# motor.net
KiCad netlist of a schematic drawn in Altium Designer
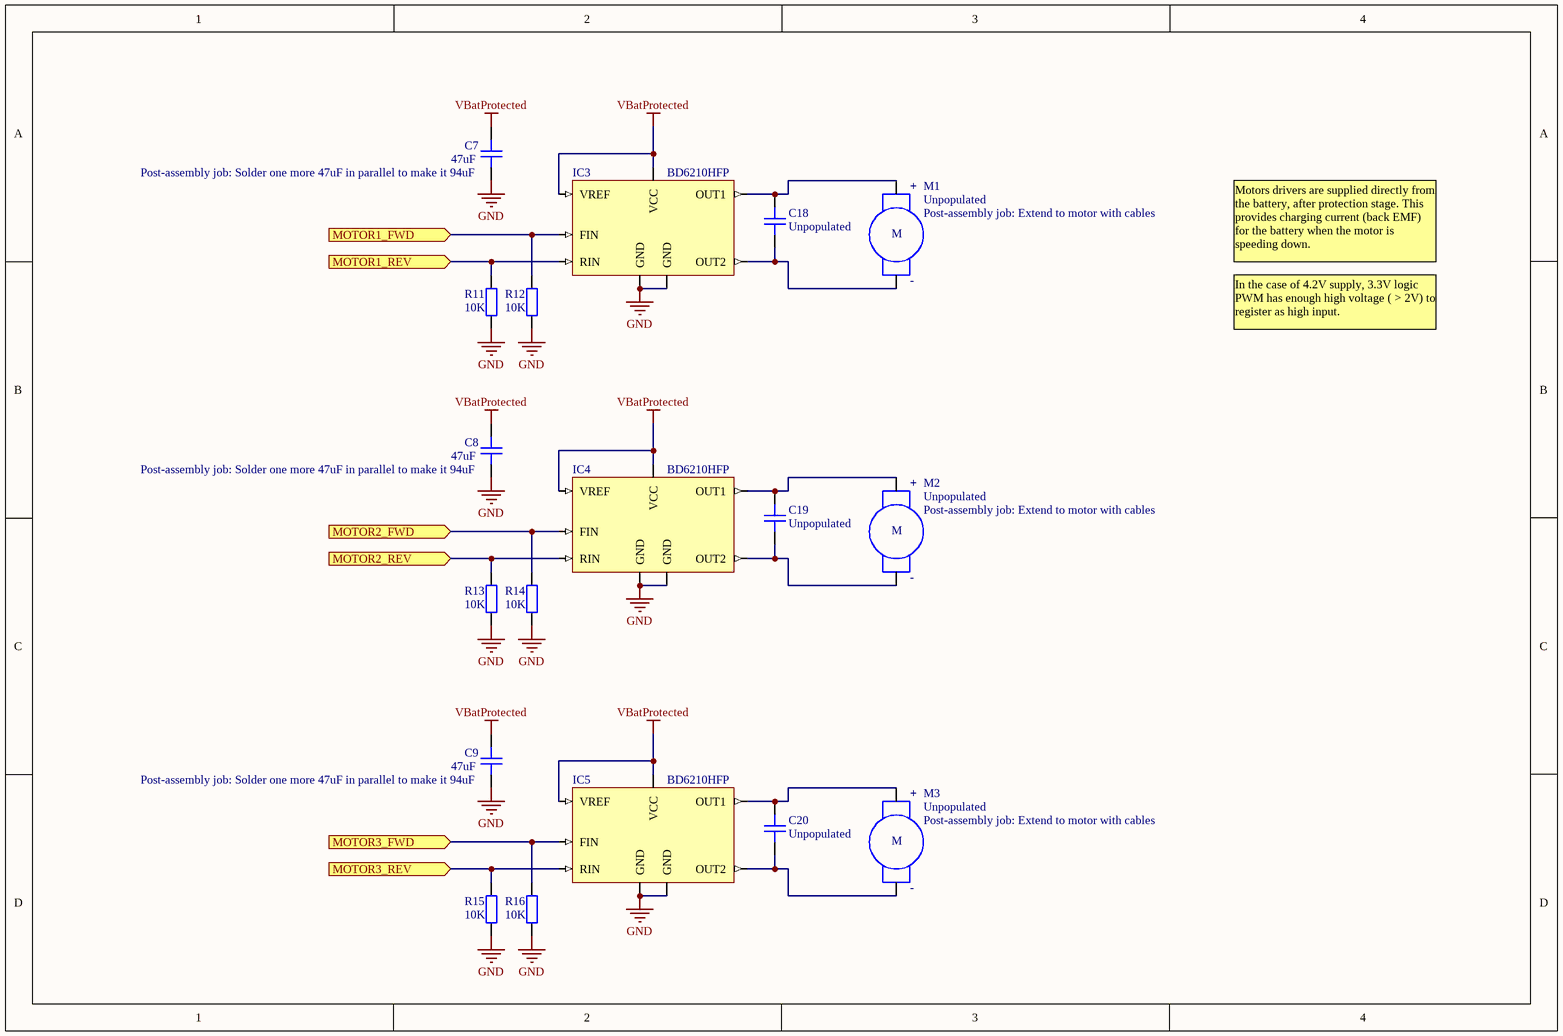
[diagram p0: motor.SchDoc]

(export (version "E")
  (design (tool "Eeschema 10.0.6"))
  (components
    (comp (ref "C7")
      (value "47uF")
      (footprint "TwoTerminal:2012[0805]_M")
      (description "Generic Capacitor")
      (fields (field (name "POST-ASSEMBLY JOB") "Solder one more 47uF in parallel to make it 94uF"))
      (libsource (lib "Passive") (part "Capacitor"))
    )
    (comp (ref "C8")
      (value "47uF")
      (footprint "TwoTerminal:2012[0805]_M")
      (description "Generic Capacitor")
      (fields (field (name "POST-ASSEMBLY JOB") "Solder one more 47uF in parallel to make it 94uF"))
      (libsource (lib "Passive") (part "Capacitor"))
    )
    (comp (ref "C9")
      (value "47uF")
      (footprint "TwoTerminal:2012[0805]_M")
      (description "Generic Capacitor")
      (fields (field (name "POST-ASSEMBLY JOB") "Solder one more 47uF in parallel to make it 94uF"))
      (libsource (lib "Passive") (part "Capacitor"))
    )
    (comp (ref "C18")
      (value "Unpopulated")
      (footprint "TwoTerminal:2012[0805]_M")
      (description "Generic Capacitor")
      (libsource (lib "Passive") (part "Capacitor"))
    )
    (comp (ref "C19")
      (value "Unpopulated")
      (footprint "TwoTerminal:2012[0805]_M")
      (description "Generic Capacitor")
      (libsource (lib "Passive") (part "Capacitor"))
    )
    (comp (ref "C20")
      (value "Unpopulated")
      (footprint "TwoTerminal:2012[0805]_M")
      (description "Generic Capacitor")
      (libsource (lib "Passive") (part "Capacitor"))
    )
    (comp (ref "IC3")
      (value "BD6210HFP")
      (footprint "HRP7_N")
      (description "DC Motor driver, full H-bridge")
      (libsource (lib "MotorDriver") (part "BD621xHFP"))
    )
    (comp (ref "IC4")
      (value "BD6210HFP")
      (footprint "HRP7_N")
      (description "DC Motor driver, full H-bridge")
      (libsource (lib "MotorDriver") (part "BD621xHFP"))
    )
    (comp (ref "IC5")
      (value "BD6210HFP")
      (footprint "HRP7_N")
      (description "DC Motor driver, full H-bridge")
      (libsource (lib "MotorDriver") (part "BD621xHFP"))
    )
    (comp (ref "M1")
      (value "Unpopulated")
      (footprint "CABLE-TERMINAL1x2")
      (description "Generic DC motor")
      (fields (field (name "POST-ASSEMBLY JOB") "Extend to motor with cables"))
      (libsource (lib "Motor") (part "DCMotor"))
    )
    (comp (ref "M2")
      (value "Unpopulated")
      (footprint "CABLE-TERMINAL1x2")
      (description "Generic DC motor")
      (fields (field (name "POST-ASSEMBLY JOB") "Extend to motor with cables"))
      (libsource (lib "Motor") (part "DCMotor"))
    )
    (comp (ref "M3")
      (value "Unpopulated")
      (footprint "CABLE-TERMINAL1x2")
      (description "Generic DC motor")
      (fields (field (name "POST-ASSEMBLY JOB") "Extend to motor with cables"))
      (libsource (lib "Motor") (part "DCMotor"))
    )
    (comp (ref "R11")
      (value "10K")
      (footprint "TwoTerminal:1608[0603]_M")
      (description "Generic Resistor")
      (libsource (lib "Passive") (part "Resistor"))
    )
    (comp (ref "R12")
      (value "10K")
      (footprint "TwoTerminal:1608[0603]_M")
      (description "Generic Resistor")
      (libsource (lib "Passive") (part "Resistor"))
    )
    (comp (ref "R13")
      (value "10K")
      (footprint "TwoTerminal:1608[0603]_M")
      (description "Generic Resistor")
      (libsource (lib "Passive") (part "Resistor"))
    )
    (comp (ref "R14")
      (value "10K")
      (footprint "TwoTerminal:1608[0603]_M")
      (description "Generic Resistor")
      (libsource (lib "Passive") (part "Resistor"))
    )
    (comp (ref "R15")
      (value "10K")
      (footprint "TwoTerminal:1608[0603]_M")
      (description "Generic Resistor")
      (libsource (lib "Passive") (part "Resistor"))
    )
    (comp (ref "R16")
      (value "10K")
      (footprint "TwoTerminal:1608[0603]_M")
      (description "Generic Resistor")
      (libsource (lib "Passive") (part "Resistor"))
    )
  )
  (nets
    (net (code "1") (name "/MOTOR1_FWD") (class "Default")
      (node (ref "IC3") (pin "3") (pinfunction "FIN_3") (pintype "input"))
      (node (ref "R12") (pin "2") (pinfunction "2_2") (pintype "passive"))
    )
    (net (code "2") (name "/MOTOR1_REV") (class "Default")
      (node (ref "IC3") (pin "5") (pinfunction "RIN_5") (pintype "input"))
      (node (ref "R11") (pin "2") (pinfunction "2_2") (pintype "passive"))
    )
    (net (code "3") (name "/MOTOR2_FWD") (class "Default")
      (node (ref "IC4") (pin "3") (pinfunction "FIN_3") (pintype "input"))
      (node (ref "R14") (pin "2") (pinfunction "2_2") (pintype "passive"))
    )
    (net (code "4") (name "/MOTOR2_REV") (class "Default")
      (node (ref "IC4") (pin "5") (pinfunction "RIN_5") (pintype "input"))
      (node (ref "R13") (pin "2") (pinfunction "2_2") (pintype "passive"))
    )
    (net (code "5") (name "/MOTOR3_FWD") (class "Default")
      (node (ref "IC5") (pin "3") (pinfunction "FIN_3") (pintype "input"))
      (node (ref "R16") (pin "2") (pinfunction "2_2") (pintype "passive"))
    )
    (net (code "6") (name "/MOTOR3_REV") (class "Default")
      (node (ref "IC5") (pin "5") (pinfunction "RIN_5") (pintype "input"))
      (node (ref "R15") (pin "2") (pinfunction "2_2") (pintype "passive"))
    )
    (net (code "7") (name "GND") (class "Default")
      (node (ref "C7") (pin "1") (pinfunction "1_1") (pintype "passive"))
      (node (ref "C8") (pin "1") (pinfunction "1_1") (pintype "passive"))
      (node (ref "C9") (pin "1") (pinfunction "1_1") (pintype "passive"))
      (node (ref "IC3") (pin "4") (pinfunction "GND_4") (pintype "power_in"))
      (node (ref "IC3") (pin "Heatsink") (pinfunction "GND_Heatsink") (pintype "power_in"))
      (node (ref "IC4") (pin "4") (pinfunction "GND_4") (pintype "power_in"))
      (node (ref "IC4") (pin "Heatsink") (pinfunction "GND_Heatsink") (pintype "power_in"))
      (node (ref "IC5") (pin "4") (pinfunction "GND_4") (pintype "power_in"))
      (node (ref "IC5") (pin "Heatsink") (pinfunction "GND_Heatsink") (pintype "power_in"))
      (node (ref "R11") (pin "1") (pinfunction "1_1") (pintype "passive"))
      (node (ref "R12") (pin "1") (pinfunction "1_1") (pintype "passive"))
      (node (ref "R13") (pin "1") (pinfunction "1_1") (pintype "passive"))
      (node (ref "R14") (pin "1") (pinfunction "1_1") (pintype "passive"))
      (node (ref "R15") (pin "1") (pinfunction "1_1") (pintype "passive"))
      (node (ref "R16") (pin "1") (pinfunction "1_1") (pintype "passive"))
    )
    (net (code "8") (name "Net-(IC3-OUT1)") (class "Default")
      (node (ref "C18") (pin "2") (pinfunction "2_2") (pintype "passive"))
      (node (ref "IC3") (pin "2") (pinfunction "OUT1_2") (pintype "output"))
      (node (ref "M1") (pin "+") (pinfunction "+_+") (pintype "passive"))
    )
    (net (code "9") (name "Net-(IC3-OUT2)") (class "Default")
      (node (ref "C18") (pin "1") (pinfunction "1_1") (pintype "passive"))
      (node (ref "IC3") (pin "6") (pinfunction "OUT2_6") (pintype "output"))
      (node (ref "M1") (pin "-") (pinfunction "-_-") (pintype "passive"))
    )
    (net (code "10") (name "Net-(IC4-OUT1)") (class "Default")
      (node (ref "C19") (pin "2") (pinfunction "2_2") (pintype "passive"))
      (node (ref "IC4") (pin "2") (pinfunction "OUT1_2") (pintype "output"))
      (node (ref "M2") (pin "+") (pinfunction "+_+") (pintype "passive"))
    )
    (net (code "11") (name "Net-(IC4-OUT2)") (class "Default")
      (node (ref "C19") (pin "1") (pinfunction "1_1") (pintype "passive"))
      (node (ref "IC4") (pin "6") (pinfunction "OUT2_6") (pintype "output"))
      (node (ref "M2") (pin "-") (pinfunction "-_-") (pintype "passive"))
    )
    (net (code "12") (name "Net-(IC5-OUT1)") (class "Default")
      (node (ref "C20") (pin "2") (pinfunction "2_2") (pintype "passive"))
      (node (ref "IC5") (pin "2") (pinfunction "OUT1_2") (pintype "output"))
      (node (ref "M3") (pin "+") (pinfunction "+_+") (pintype "passive"))
    )
    (net (code "13") (name "Net-(IC5-OUT2)") (class "Default")
      (node (ref "C20") (pin "1") (pinfunction "1_1") (pintype "passive"))
      (node (ref "IC5") (pin "6") (pinfunction "OUT2_6") (pintype "output"))
      (node (ref "M3") (pin "-") (pinfunction "-_-") (pintype "passive"))
    )
    (net (code "14") (name "VBatProtected") (class "Default")
      (node (ref "C7") (pin "2") (pinfunction "2_2") (pintype "passive"))
      (node (ref "C8") (pin "2") (pinfunction "2_2") (pintype "passive"))
      (node (ref "C9") (pin "2") (pinfunction "2_2") (pintype "passive"))
      (node (ref "IC3") (pin "1") (pinfunction "VREF_1") (pintype "input"))
      (node (ref "IC3") (pin "7") (pinfunction "VCC_7") (pintype "power_in"))
      (node (ref "IC4") (pin "1") (pinfunction "VREF_1") (pintype "input"))
      (node (ref "IC4") (pin "7") (pinfunction "VCC_7") (pintype "power_in"))
      (node (ref "IC5") (pin "1") (pinfunction "VREF_1") (pintype "input"))
      (node (ref "IC5") (pin "7") (pinfunction "VCC_7") (pintype "power_in"))
    )
  )
)
